# 12vOutputs.net
KiCad netlist of a schematic drawn in Altium Designer
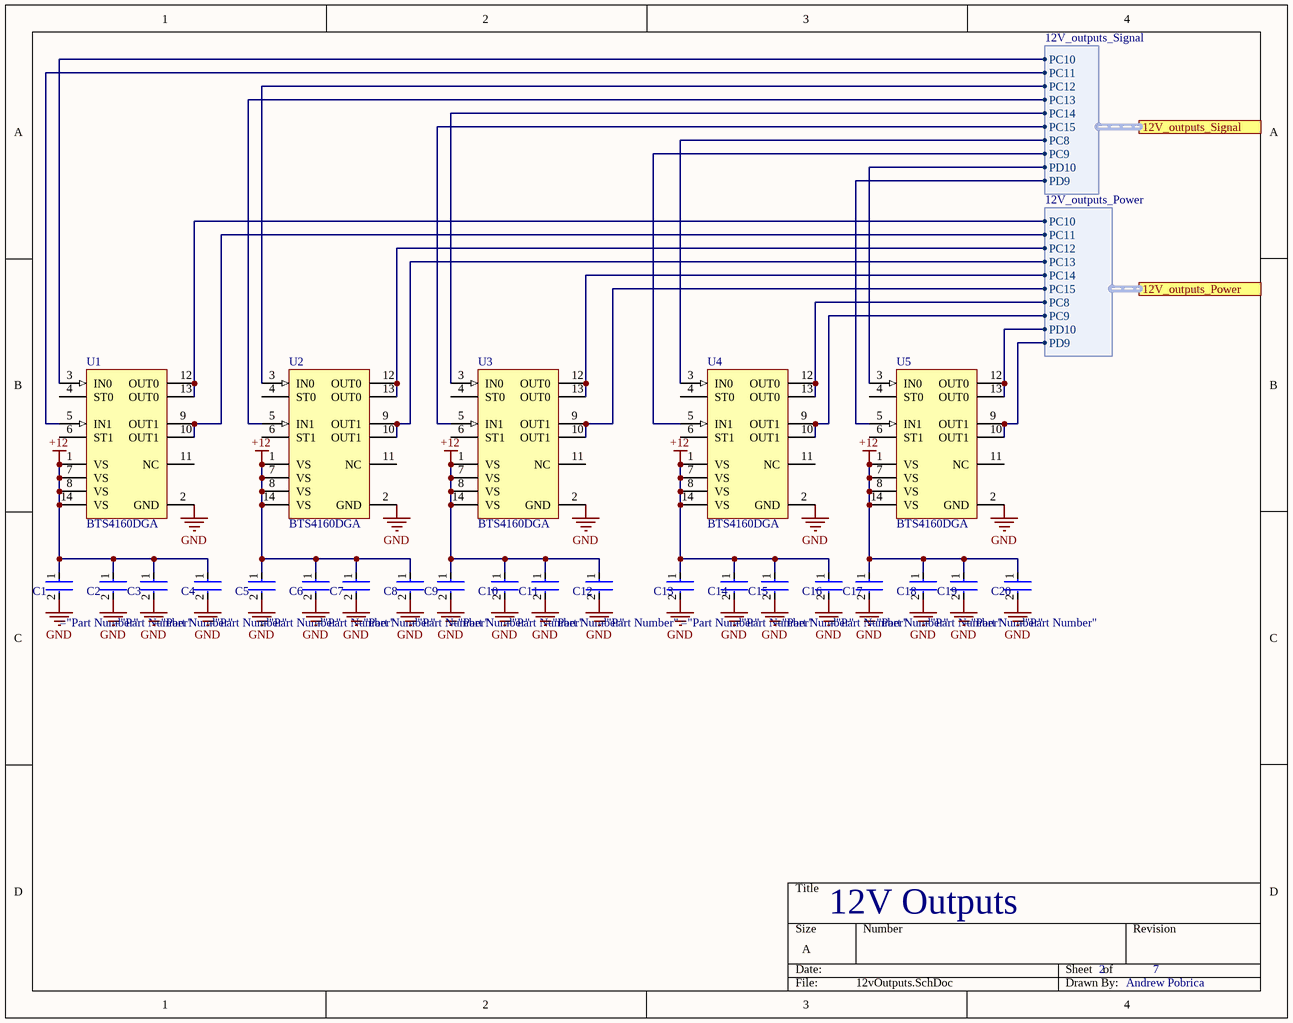
[diagram p0: 12vOutputs.SchDoc]

(export (version "E")
  (design (tool "Eeschema 10.0.6"))
  (components
    (comp (ref "C1")
      (value "C0603C104K5RACTU")
      (footprint "Kemet_C0805_IPC_A")
      (libsource (lib "UNK_Kemet_C0603C104K5RACTU_eec") (part "C0603C104K5RACTU"))
    )
    (comp (ref "C2")
      (value "C0603C104K5RACTU")
      (footprint "Kemet_C0805_IPC_A")
      (libsource (lib "UNK_Kemet_C0603C104K5RACTU_eec") (part "C0603C104K5RACTU"))
    )
    (comp (ref "C3")
      (value "C0603C104K5RACTU")
      (footprint "Kemet_C0805_IPC_A")
      (libsource (lib "UNK_Kemet_C0603C104K5RACTU_eec") (part "C0603C104K5RACTU"))
    )
    (comp (ref "C4")
      (value "C0603C104K5RACTU")
      (footprint "Kemet_C0805_IPC_A")
      (libsource (lib "UNK_Kemet_C0603C104K5RACTU_eec") (part "C0603C104K5RACTU"))
    )
    (comp (ref "C5")
      (value "C0603C104K5RACTU")
      (footprint "Kemet_C0805_IPC_A")
      (libsource (lib "UNK_Kemet_C0603C104K5RACTU_eec") (part "C0603C104K5RACTU"))
    )
    (comp (ref "C6")
      (value "C0603C104K5RACTU")
      (footprint "Kemet_C0805_IPC_A")
      (libsource (lib "UNK_Kemet_C0603C104K5RACTU_eec") (part "C0603C104K5RACTU"))
    )
    (comp (ref "C7")
      (value "C0603C104K5RACTU")
      (footprint "Kemet_C0805_IPC_A")
      (libsource (lib "UNK_Kemet_C0603C104K5RACTU_eec") (part "C0603C104K5RACTU"))
    )
    (comp (ref "C8")
      (value "C0603C104K5RACTU")
      (footprint "Kemet_C0805_IPC_A")
      (libsource (lib "UNK_Kemet_C0603C104K5RACTU_eec") (part "C0603C104K5RACTU"))
    )
    (comp (ref "C9")
      (value "C0603C104K5RACTU")
      (footprint "Kemet_C0805_IPC_A")
      (libsource (lib "UNK_Kemet_C0603C104K5RACTU_eec") (part "C0603C104K5RACTU"))
    )
    (comp (ref "C10")
      (value "C0603C104K5RACTU")
      (footprint "Kemet_C0805_IPC_A")
      (libsource (lib "UNK_Kemet_C0603C104K5RACTU_eec") (part "C0603C104K5RACTU"))
    )
    (comp (ref "C11")
      (value "C0603C104K5RACTU")
      (footprint "Kemet_C0805_IPC_A")
      (libsource (lib "UNK_Kemet_C0603C104K5RACTU_eec") (part "C0603C104K5RACTU"))
    )
    (comp (ref "C12")
      (value "C0603C104K5RACTU")
      (footprint "Kemet_C0805_IPC_A")
      (libsource (lib "UNK_Kemet_C0603C104K5RACTU_eec") (part "C0603C104K5RACTU"))
    )
    (comp (ref "C13")
      (value "C0603C104K5RACTU")
      (footprint "Kemet_C0805_IPC_A")
      (libsource (lib "UNK_Kemet_C0603C104K5RACTU_eec") (part "C0603C104K5RACTU"))
    )
    (comp (ref "C14")
      (value "C0603C104K5RACTU")
      (footprint "Kemet_C0805_IPC_A")
      (libsource (lib "UNK_Kemet_C0603C104K5RACTU_eec") (part "C0603C104K5RACTU"))
    )
    (comp (ref "C15")
      (value "C0603C104K5RACTU")
      (footprint "Kemet_C0805_IPC_A")
      (libsource (lib "UNK_Kemet_C0603C104K5RACTU_eec") (part "C0603C104K5RACTU"))
    )
    (comp (ref "C16")
      (value "C0603C104K5RACTU")
      (footprint "Kemet_C0805_IPC_A")
      (libsource (lib "UNK_Kemet_C0603C104K5RACTU_eec") (part "C0603C104K5RACTU"))
    )
    (comp (ref "C17")
      (value "C0603C104K5RACTU")
      (footprint "Kemet_C0805_IPC_A")
      (libsource (lib "UNK_Kemet_C0603C104K5RACTU_eec") (part "C0603C104K5RACTU"))
    )
    (comp (ref "C18")
      (value "C0603C104K5RACTU")
      (footprint "Kemet_C0805_IPC_A")
      (libsource (lib "UNK_Kemet_C0603C104K5RACTU_eec") (part "C0603C104K5RACTU"))
    )
    (comp (ref "C19")
      (value "C0603C104K5RACTU")
      (footprint "Kemet_C0805_IPC_A")
      (libsource (lib "UNK_Kemet_C0603C104K5RACTU_eec") (part "C0603C104K5RACTU"))
    )
    (comp (ref "C20")
      (value "C0603C104K5RACTU")
      (footprint "Kemet_C0805_IPC_A")
      (libsource (lib "UNK_Kemet_C0603C104K5RACTU_eec") (part "C0603C104K5RACTU"))
    )
    (comp (ref "U1")
      (value "BTS4160DGA")
      (footprint "INF-PG-DSO-14-37_N")
      (fields (field (name "MANUFACTURER") "Infineon"))
      (libsource (lib "Infineon_BTS4160DGA") (part "BTS4160DGA"))
    )
    (comp (ref "U2")
      (value "BTS4160DGA")
      (footprint "INF-PG-DSO-14-37_N")
      (fields (field (name "MANUFACTURER") "Infineon"))
      (libsource (lib "Infineon_BTS4160DGA") (part "BTS4160DGA"))
    )
    (comp (ref "U3")
      (value "BTS4160DGA")
      (footprint "INF-PG-DSO-14-37_N")
      (fields (field (name "MANUFACTURER") "Infineon"))
      (libsource (lib "Infineon_BTS4160DGA") (part "BTS4160DGA"))
    )
    (comp (ref "U4")
      (value "BTS4160DGA")
      (footprint "INF-PG-DSO-14-37_N")
      (fields (field (name "MANUFACTURER") "Infineon"))
      (libsource (lib "Infineon_BTS4160DGA") (part "BTS4160DGA"))
    )
    (comp (ref "U5")
      (value "BTS4160DGA")
      (footprint "INF-PG-DSO-14-37_N")
      (fields (field (name "MANUFACTURER") "Infineon"))
      (libsource (lib "Infineon_BTS4160DGA") (part "BTS4160DGA"))
    )
  )
  (nets
    (net (code "3") (name "+12") (class "Default")
      (node (ref "C1") (pin "1") (pinfunction "1_1") (pintype "passive"))
      (node (ref "C10") (pin "1") (pinfunction "1_1") (pintype "passive"))
      (node (ref "C11") (pin "1") (pinfunction "1_1") (pintype "passive"))
      (node (ref "C12") (pin "1") (pinfunction "1_1") (pintype "passive"))
      (node (ref "C13") (pin "1") (pinfunction "1_1") (pintype "passive"))
      (node (ref "C14") (pin "1") (pinfunction "1_1") (pintype "passive"))
      (node (ref "C15") (pin "1") (pinfunction "1_1") (pintype "passive"))
      (node (ref "C16") (pin "1") (pinfunction "1_1") (pintype "passive"))
      (node (ref "C17") (pin "1") (pinfunction "1_1") (pintype "passive"))
      (node (ref "C18") (pin "1") (pinfunction "1_1") (pintype "passive"))
      (node (ref "C19") (pin "1") (pinfunction "1_1") (pintype "passive"))
      (node (ref "C2") (pin "1") (pinfunction "1_1") (pintype "passive"))
      (node (ref "C20") (pin "1") (pinfunction "1_1") (pintype "passive"))
      (node (ref "C3") (pin "1") (pinfunction "1_1") (pintype "passive"))
      (node (ref "C4") (pin "1") (pinfunction "1_1") (pintype "passive"))
      (node (ref "C5") (pin "1") (pinfunction "1_1") (pintype "passive"))
      (node (ref "C6") (pin "1") (pinfunction "1_1") (pintype "passive"))
      (node (ref "C7") (pin "1") (pinfunction "1_1") (pintype "passive"))
      (node (ref "C8") (pin "1") (pinfunction "1_1") (pintype "passive"))
      (node (ref "C9") (pin "1") (pinfunction "1_1") (pintype "passive"))
      (node (ref "U1") (pin "1") (pinfunction "VS_1") (pintype "power_in"))
      (node (ref "U1") (pin "14") (pinfunction "VS_14") (pintype "power_in"))
      (node (ref "U1") (pin "7") (pinfunction "VS_7") (pintype "power_in"))
      (node (ref "U1") (pin "8") (pinfunction "VS_8") (pintype "power_in"))
      (node (ref "U2") (pin "1") (pinfunction "VS_1") (pintype "power_in"))
      (node (ref "U2") (pin "14") (pinfunction "VS_14") (pintype "power_in"))
      (node (ref "U2") (pin "7") (pinfunction "VS_7") (pintype "power_in"))
      (node (ref "U2") (pin "8") (pinfunction "VS_8") (pintype "power_in"))
      (node (ref "U3") (pin "1") (pinfunction "VS_1") (pintype "power_in"))
      (node (ref "U3") (pin "14") (pinfunction "VS_14") (pintype "power_in"))
      (node (ref "U3") (pin "7") (pinfunction "VS_7") (pintype "power_in"))
      (node (ref "U3") (pin "8") (pinfunction "VS_8") (pintype "power_in"))
      (node (ref "U4") (pin "1") (pinfunction "VS_1") (pintype "power_in"))
      (node (ref "U4") (pin "14") (pinfunction "VS_14") (pintype "power_in"))
      (node (ref "U4") (pin "7") (pinfunction "VS_7") (pintype "power_in"))
      (node (ref "U4") (pin "8") (pinfunction "VS_8") (pintype "power_in"))
      (node (ref "U5") (pin "1") (pinfunction "VS_1") (pintype "power_in"))
      (node (ref "U5") (pin "14") (pinfunction "VS_14") (pintype "power_in"))
      (node (ref "U5") (pin "7") (pinfunction "VS_7") (pintype "power_in"))
      (node (ref "U5") (pin "8") (pinfunction "VS_8") (pintype "power_in"))
    )
    (net (code "6") (name "GND") (class "Default")
      (node (ref "C1") (pin "2") (pinfunction "2_2") (pintype "passive"))
      (node (ref "C10") (pin "2") (pinfunction "2_2") (pintype "passive"))
      (node (ref "C11") (pin "2") (pinfunction "2_2") (pintype "passive"))
      (node (ref "C12") (pin "2") (pinfunction "2_2") (pintype "passive"))
      (node (ref "C13") (pin "2") (pinfunction "2_2") (pintype "passive"))
      (node (ref "C14") (pin "2") (pinfunction "2_2") (pintype "passive"))
      (node (ref "C15") (pin "2") (pinfunction "2_2") (pintype "passive"))
      (node (ref "C16") (pin "2") (pinfunction "2_2") (pintype "passive"))
      (node (ref "C17") (pin "2") (pinfunction "2_2") (pintype "passive"))
      (node (ref "C18") (pin "2") (pinfunction "2_2") (pintype "passive"))
      (node (ref "C19") (pin "2") (pinfunction "2_2") (pintype "passive"))
      (node (ref "C2") (pin "2") (pinfunction "2_2") (pintype "passive"))
      (node (ref "C20") (pin "2") (pinfunction "2_2") (pintype "passive"))
      (node (ref "C3") (pin "2") (pinfunction "2_2") (pintype "passive"))
      (node (ref "C4") (pin "2") (pinfunction "2_2") (pintype "passive"))
      (node (ref "C5") (pin "2") (pinfunction "2_2") (pintype "passive"))
      (node (ref "C6") (pin "2") (pinfunction "2_2") (pintype "passive"))
      (node (ref "C7") (pin "2") (pinfunction "2_2") (pintype "passive"))
      (node (ref "C8") (pin "2") (pinfunction "2_2") (pintype "passive"))
      (node (ref "C9") (pin "2") (pinfunction "2_2") (pintype "passive"))
      (node (ref "U1") (pin "2") (pinfunction "GND_2") (pintype "power_in"))
      (node (ref "U2") (pin "2") (pinfunction "GND_2") (pintype "power_in"))
      (node (ref "U3") (pin "2") (pinfunction "GND_2") (pintype "power_in"))
      (node (ref "U4") (pin "2") (pinfunction "GND_2") (pintype "power_in"))
      (node (ref "U5") (pin "2") (pinfunction "GND_2") (pintype "power_in"))
    )
    (net (code "7") (name "Net-(U1-OUT0-Pad12)") (class "Default")
      (node (ref "U1") (pin "12") (pinfunction "OUT0_12") (pintype "power_in"))
      (node (ref "U1") (pin "13") (pinfunction "OUT0_13") (pintype "power_in"))
    )
    (net (code "8") (name "Net-(U1-OUT1-Pad10)") (class "Default")
      (node (ref "U1") (pin "10") (pinfunction "OUT1_10") (pintype "power_in"))
      (node (ref "U1") (pin "9") (pinfunction "OUT1_9") (pintype "power_in"))
    )
    (net (code "9") (name "Net-(U2-OUT0-Pad12)") (class "Default")
      (node (ref "U2") (pin "12") (pinfunction "OUT0_12") (pintype "power_in"))
      (node (ref "U2") (pin "13") (pinfunction "OUT0_13") (pintype "power_in"))
    )
    (net (code "10") (name "Net-(U2-OUT1-Pad10)") (class "Default")
      (node (ref "U2") (pin "10") (pinfunction "OUT1_10") (pintype "power_in"))
      (node (ref "U2") (pin "9") (pinfunction "OUT1_9") (pintype "power_in"))
    )
    (net (code "11") (name "Net-(U3-OUT0-Pad12)") (class "Default")
      (node (ref "U3") (pin "12") (pinfunction "OUT0_12") (pintype "power_in"))
      (node (ref "U3") (pin "13") (pinfunction "OUT0_13") (pintype "power_in"))
    )
    (net (code "12") (name "Net-(U3-OUT1-Pad10)") (class "Default")
      (node (ref "U3") (pin "10") (pinfunction "OUT1_10") (pintype "power_in"))
      (node (ref "U3") (pin "9") (pinfunction "OUT1_9") (pintype "power_in"))
    )
    (net (code "13") (name "Net-(U4-OUT0-Pad12)") (class "Default")
      (node (ref "U4") (pin "12") (pinfunction "OUT0_12") (pintype "power_in"))
      (node (ref "U4") (pin "13") (pinfunction "OUT0_13") (pintype "power_in"))
    )
    (net (code "14") (name "Net-(U4-OUT1-Pad10)") (class "Default")
      (node (ref "U4") (pin "10") (pinfunction "OUT1_10") (pintype "power_in"))
      (node (ref "U4") (pin "9") (pinfunction "OUT1_9") (pintype "power_in"))
    )
    (net (code "15") (name "Net-(U5-OUT0-Pad12)") (class "Default")
      (node (ref "U5") (pin "12") (pinfunction "OUT0_12") (pintype "power_in"))
      (node (ref "U5") (pin "13") (pinfunction "OUT0_13") (pintype "power_in"))
    )
    (net (code "16") (name "Net-(U5-OUT1-Pad10)") (class "Default")
      (node (ref "U5") (pin "10") (pinfunction "OUT1_10") (pintype "power_in"))
      (node (ref "U5") (pin "9") (pinfunction "OUT1_9") (pintype "power_in"))
    )
    (net (code "17") (name "unconnected-(U1-IN0-Pad3)") (class "Default")
      (node (ref "U1") (pin "3") (pinfunction "IN0_3") (pintype "input"))
    )
    (net (code "18") (name "unconnected-(U1-IN1-Pad5)") (class "Default")
      (node (ref "U1") (pin "5") (pinfunction "IN1_5") (pintype "input"))
    )
    (net (code "19") (name "unconnected-(U1-NC-Pad11)") (class "Default")
      (node (ref "U1") (pin "11") (pinfunction "NC_11") (pintype "passive"))
    )
    (net (code "20") (name "unconnected-(U1-ST0-Pad4)") (class "Default")
      (node (ref "U1") (pin "4") (pinfunction "ST0_4") (pintype "open_collector"))
    )
    (net (code "21") (name "unconnected-(U1-ST1-Pad6)") (class "Default")
      (node (ref "U1") (pin "6") (pinfunction "ST1_6") (pintype "open_collector"))
    )
    (net (code "22") (name "unconnected-(U2-IN0-Pad3)") (class "Default")
      (node (ref "U2") (pin "3") (pinfunction "IN0_3") (pintype "input"))
    )
    (net (code "23") (name "unconnected-(U2-IN1-Pad5)") (class "Default")
      (node (ref "U2") (pin "5") (pinfunction "IN1_5") (pintype "input"))
    )
    (net (code "24") (name "unconnected-(U2-NC-Pad11)") (class "Default")
      (node (ref "U2") (pin "11") (pinfunction "NC_11") (pintype "passive"))
    )
    (net (code "25") (name "unconnected-(U2-ST0-Pad4)") (class "Default")
      (node (ref "U2") (pin "4") (pinfunction "ST0_4") (pintype "open_collector"))
    )
    (net (code "26") (name "unconnected-(U2-ST1-Pad6)") (class "Default")
      (node (ref "U2") (pin "6") (pinfunction "ST1_6") (pintype "open_collector"))
    )
    (net (code "27") (name "unconnected-(U3-IN0-Pad3)") (class "Default")
      (node (ref "U3") (pin "3") (pinfunction "IN0_3") (pintype "input"))
    )
    (net (code "28") (name "unconnected-(U3-IN1-Pad5)") (class "Default")
      (node (ref "U3") (pin "5") (pinfunction "IN1_5") (pintype "input"))
    )
    (net (code "29") (name "unconnected-(U3-NC-Pad11)") (class "Default")
      (node (ref "U3") (pin "11") (pinfunction "NC_11") (pintype "passive"))
    )
    (net (code "30") (name "unconnected-(U3-ST0-Pad4)") (class "Default")
      (node (ref "U3") (pin "4") (pinfunction "ST0_4") (pintype "open_collector"))
    )
    (net (code "31") (name "unconnected-(U3-ST1-Pad6)") (class "Default")
      (node (ref "U3") (pin "6") (pinfunction "ST1_6") (pintype "open_collector"))
    )
    (net (code "32") (name "unconnected-(U4-IN0-Pad3)") (class "Default")
      (node (ref "U4") (pin "3") (pinfunction "IN0_3") (pintype "input"))
    )
    (net (code "33") (name "unconnected-(U4-IN1-Pad5)") (class "Default")
      (node (ref "U4") (pin "5") (pinfunction "IN1_5") (pintype "input"))
    )
    (net (code "34") (name "unconnected-(U4-NC-Pad11)") (class "Default")
      (node (ref "U4") (pin "11") (pinfunction "NC_11") (pintype "passive"))
    )
    (net (code "35") (name "unconnected-(U4-ST0-Pad4)") (class "Default")
      (node (ref "U4") (pin "4") (pinfunction "ST0_4") (pintype "open_collector"))
    )
    (net (code "36") (name "unconnected-(U4-ST1-Pad6)") (class "Default")
      (node (ref "U4") (pin "6") (pinfunction "ST1_6") (pintype "open_collector"))
    )
    (net (code "37") (name "unconnected-(U5-IN0-Pad3)") (class "Default")
      (node (ref "U5") (pin "3") (pinfunction "IN0_3") (pintype "input"))
    )
    (net (code "38") (name "unconnected-(U5-IN1-Pad5)") (class "Default")
      (node (ref "U5") (pin "5") (pinfunction "IN1_5") (pintype "input"))
    )
    (net (code "39") (name "unconnected-(U5-NC-Pad11)") (class "Default")
      (node (ref "U5") (pin "11") (pinfunction "NC_11") (pintype "passive"))
    )
    (net (code "40") (name "unconnected-(U5-ST0-Pad4)") (class "Default")
      (node (ref "U5") (pin "4") (pinfunction "ST0_4") (pintype "open_collector"))
    )
    (net (code "41") (name "unconnected-(U5-ST1-Pad6)") (class "Default")
      (node (ref "U5") (pin "6") (pinfunction "ST1_6") (pintype "open_collector"))
    )
  )
)
